# littleWire-PTH.net
KiCad netlist of a schematic drawn in EAGLE
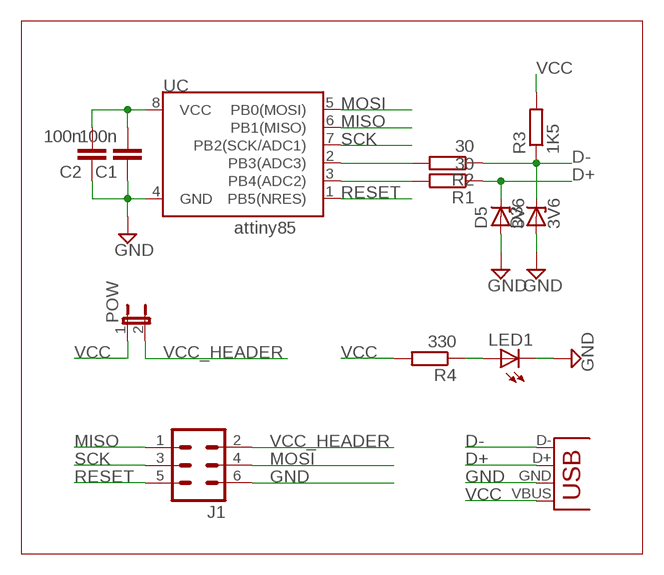
[diagram p0: schematic, sheet 1]

(export (version "E")
  (design (tool "Eeschema 10.0.6"))
  (components
    (comp (ref "C1")
      (value "100n")
      (footprint "eagle-import:C025-025X050")
      (libsource (lib "eagle-import") (part "C-EU025-025X050"))
    )
    (comp (ref "C2")
      (value "100n")
      (footprint "eagle-import:C025-025X050")
      (libsource (lib "eagle-import") (part "C-EU025-025X050"))
    )
    (comp (ref "D3")
      (value "3V6")
      (footprint "eagle-import:ZDIO-2.5")
      (libsource (lib "eagle-import") (part "ZENER-DIODEZD-2.5"))
    )
    (comp (ref "D5")
      (value "3V6")
      (footprint "eagle-import:ZDIO-7.5")
      (libsource (lib "eagle-import") (part "ZENER-DIODEZD-7.5"))
    )
    (comp (ref "J1")
      (value "ML6")
      (footprint "eagle-import:ML6")
      (libsource (lib "eagle-import") (part "ML6"))
    )
    (comp (ref "LED1")
      (value "LED3MM")
      (footprint "eagle-import:LED3MM")
      (libsource (lib "eagle-import") (part "LED3MM"))
    )
    (comp (ref "POW")
      (value "JP1E")
      (footprint "eagle-import:JP1")
      (libsource (lib "eagle-import") (part "JP1E"))
    )
    (comp (ref "R1")
      (value "30")
      (footprint "eagle-import:0207_2V")
      (libsource (lib "eagle-import") (part "R-EU_0207/2V"))
    )
    (comp (ref "R2")
      (value "30")
      (footprint "eagle-import:0207_2V")
      (libsource (lib "eagle-import") (part "R-EU_0207/2V"))
    )
    (comp (ref "R3")
      (value "1K5")
      (footprint "eagle-import:0207_2V")
      (libsource (lib "eagle-import") (part "R-EU_0207/2V"))
    )
    (comp (ref "R4")
      (value "330")
      (footprint "eagle-import:0207_2V")
      (libsource (lib "eagle-import") (part "R-EU_0207/2V"))
    )
    (comp (ref "UC")
      (value "ATTINY45DIP8")
      (footprint "eagle-import:DIP08")
      (libsource (lib "eagle-import") (part "ATTINY45DIP8"))
    )
    (comp (ref "X1")
      (value "USB-A-H")
      (footprint "eagle-import:USB-A-H")
      (libsource (lib "eagle-import") (part "USB-A-H"))
    )
  )
  (nets
    (net (code "1") (name "/D+") (class "Default")
      (node (ref "D5") (pin "C") (pinfunction "C_C") (pintype "passive"))
      (node (ref "R1") (pin "1") (pinfunction "1_1") (pintype "passive"))
      (node (ref "X1") (pin "D+") (pinfunction "D-_D+") (pintype "bidirectional"))
    )
    (net (code "2") (name "/D-") (class "Default")
      (node (ref "D3") (pin "C") (pinfunction "C_C") (pintype "passive"))
      (node (ref "R2") (pin "1") (pinfunction "1_1") (pintype "passive"))
      (node (ref "R3") (pin "1") (pinfunction "1_1") (pintype "passive"))
      (node (ref "X1") (pin "D-") (pinfunction "D+_D-") (pintype "bidirectional"))
    )
    (net (code "3") (name "/MISO") (class "Default")
      (node (ref "J1") (pin "1") (pinfunction "1_1") (pintype "passive"))
      (node (ref "UC") (pin "6") (pinfunction "PB1(MISO)_6") (pintype "bidirectional"))
    )
    (net (code "4") (name "/MOSI") (class "Default")
      (node (ref "J1") (pin "4") (pinfunction "4_4") (pintype "passive"))
      (node (ref "UC") (pin "5") (pinfunction "PB0(MOSI)_5") (pintype "bidirectional"))
    )
    (net (code "5") (name "/RESET") (class "Default")
      (node (ref "J1") (pin "5") (pinfunction "5_5") (pintype "passive"))
      (node (ref "UC") (pin "1") (pinfunction "PB5(NRES)_1") (pintype "bidirectional"))
    )
    (net (code "6") (name "/SCK") (class "Default")
      (node (ref "J1") (pin "3") (pinfunction "3_3") (pintype "passive"))
      (node (ref "UC") (pin "7") (pinfunction "PB2(SCK/ADC1)_7") (pintype "bidirectional"))
    )
    (net (code "7") (name "/VCC") (class "Default")
      (node (ref "C1") (pin "2") (pinfunction "2_2") (pintype "passive"))
      (node (ref "C2") (pin "2") (pinfunction "2_2") (pintype "passive"))
      (node (ref "POW") (pin "1") (pinfunction "1_1") (pintype "passive"))
      (node (ref "R3") (pin "2") (pinfunction "2_2") (pintype "passive"))
      (node (ref "R4") (pin "2") (pinfunction "2_2") (pintype "passive"))
      (node (ref "UC") (pin "8") (pinfunction "VCC_8") (pintype "bidirectional"))
      (node (ref "X1") (pin "VBUS") (pinfunction "GND_VBUS") (pintype "bidirectional"))
    )
    (net (code "8") (name "/VCC_HEADER") (class "Default")
      (node (ref "J1") (pin "2") (pinfunction "2_2") (pintype "passive"))
      (node (ref "POW") (pin "2") (pinfunction "2_2") (pintype "passive"))
    )
    (net (code "9") (name "GND") (class "Default")
      (node (ref "C1") (pin "1") (pinfunction "1_1") (pintype "passive"))
      (node (ref "C2") (pin "1") (pinfunction "1_1") (pintype "passive"))
      (node (ref "D3") (pin "A") (pinfunction "A_A") (pintype "passive"))
      (node (ref "D5") (pin "A") (pinfunction "A_A") (pintype "passive"))
      (node (ref "J1") (pin "6") (pinfunction "6_6") (pintype "passive"))
      (node (ref "LED1") (pin "K") (pinfunction "C_K") (pintype "passive"))
      (node (ref "UC") (pin "4") (pinfunction "GND_4") (pintype "bidirectional"))
      (node (ref "X1") (pin "GND") (pinfunction "VBUS_GND") (pintype "bidirectional"))
    )
    (net (code "10") (name "Net-(LED1-PadA)") (class "Default")
      (node (ref "LED1") (pin "A") (pinfunction "A_A") (pintype "passive"))
      (node (ref "R4") (pin "1") (pinfunction "1_1") (pintype "passive"))
    )
    (net (code "11") (name "Net-(UC-PB3(ADC3))") (class "Default")
      (node (ref "R2") (pin "2") (pinfunction "2_2") (pintype "passive"))
      (node (ref "UC") (pin "2") (pinfunction "PB3(ADC3)_2") (pintype "bidirectional"))
    )
    (net (code "12") (name "Net-(UC-PB4(ADC2))") (class "Default")
      (node (ref "R1") (pin "2") (pinfunction "2_2") (pintype "passive"))
      (node (ref "UC") (pin "3") (pinfunction "PB4(ADC2)_3") (pintype "bidirectional"))
    )
  )
)
